# ANALOG_INPUT.net
KiCad netlist of a schematic drawn in Altium Designer
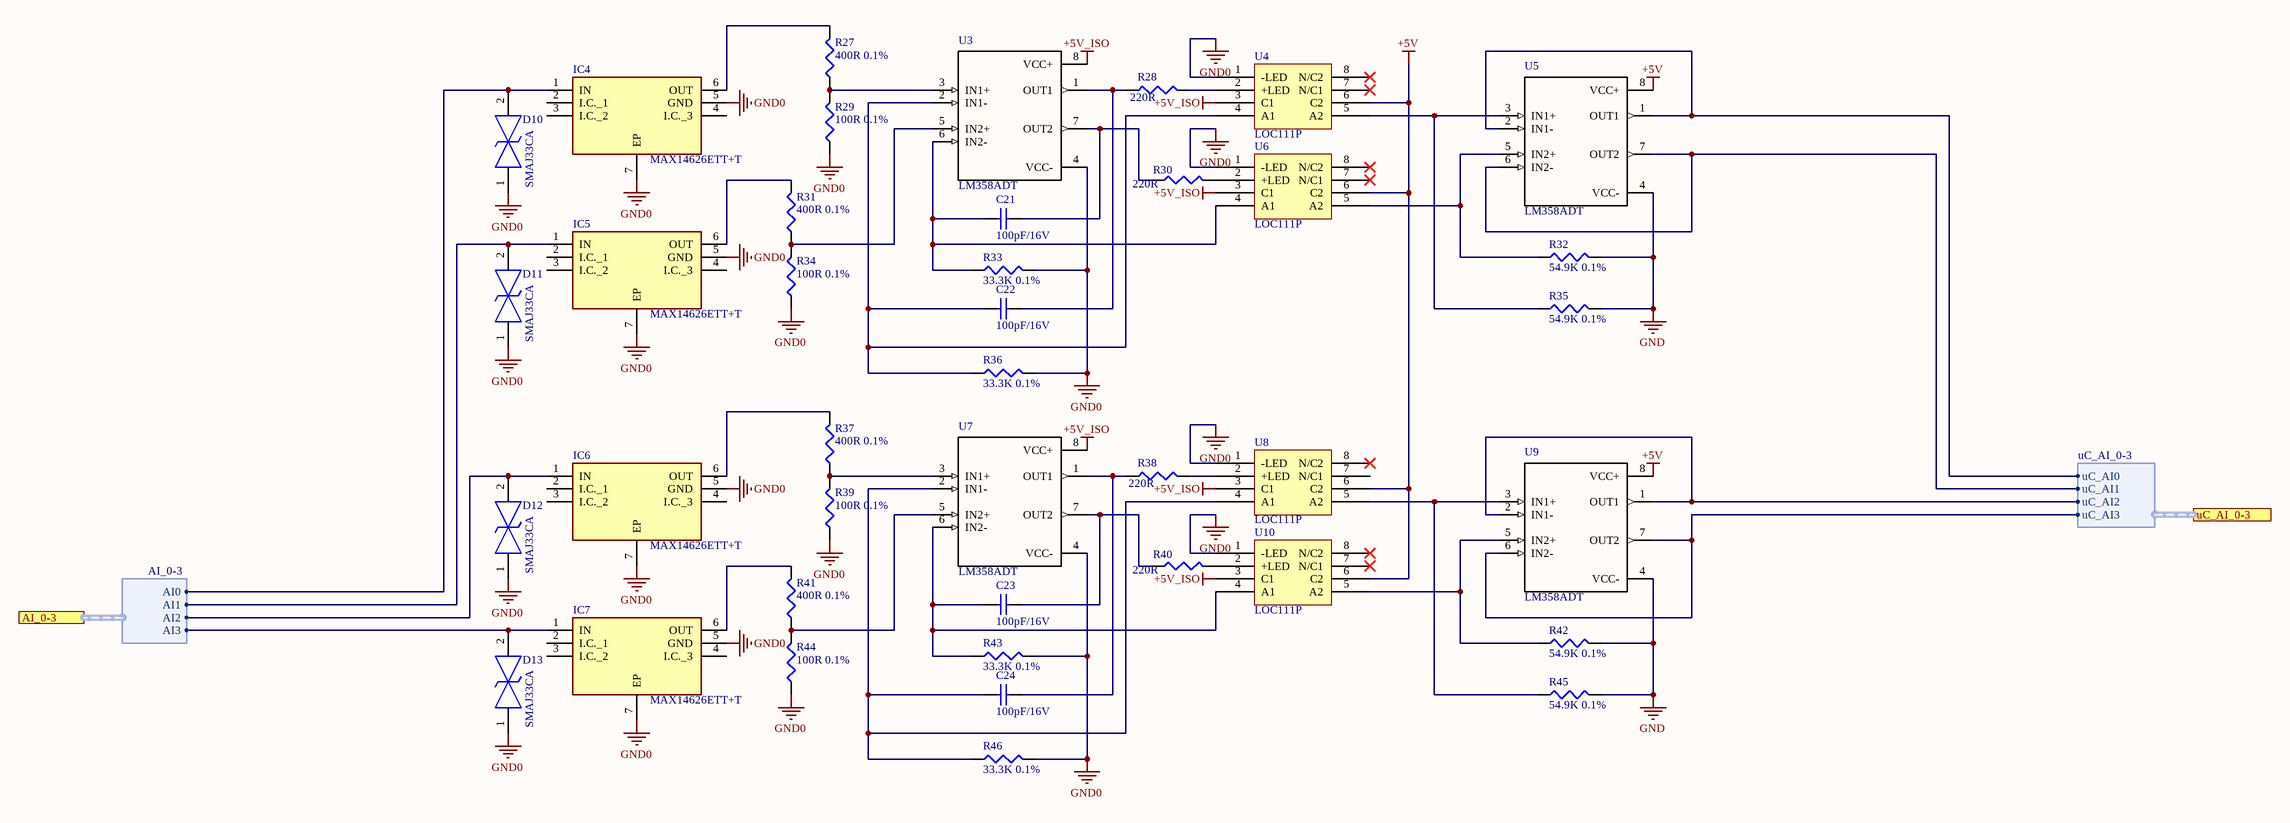
[diagram p0: ANALOG_INPUT.SchDoc]

(export (version "E")
  (design (tool "Eeschema 10.0.6"))
  (components
    (comp (ref "C21")
      (value "100pF/16V")
      (footprint "1608[0603]")
      (description "Capacitor (Semiconductor SIM Model)")
      (fields (field (name "PUBLISHER") "Altium Limited"))
      (libsource (lib "Miscellaneous Devices") (part "Cap Semi"))
    )
    (comp (ref "C22")
      (value "100pF/16V")
      (footprint "1608[0603]")
      (description "Capacitor (Semiconductor SIM Model)")
      (fields (field (name "PUBLISHER") "Altium Limited"))
      (libsource (lib "Miscellaneous Devices") (part "Cap Semi"))
    )
    (comp (ref "C23")
      (value "100pF/16V")
      (footprint "1608[0603]")
      (description "Capacitor (Semiconductor SIM Model)")
      (fields (field (name "PUBLISHER") "Altium Limited"))
      (libsource (lib "Miscellaneous Devices") (part "Cap Semi"))
    )
    (comp (ref "C24")
      (value "100pF/16V")
      (footprint "1608[0603]")
      (description "Capacitor (Semiconductor SIM Model)")
      (fields (field (name "PUBLISHER") "Altium Limited"))
      (libsource (lib "Miscellaneous Devices") (part "Cap Semi"))
    )
    (comp (ref "D10")
      (value "SMAJ33CA")
      (footprint "SamacSys:DIONM5126X250N")
      (description "TVS Diode (Bi-directional)")
      (fields (field (name "MOUSER PART NUMBER") "576-SMAJ33CA"))
      (libsource (lib "*") (part "SMAJ33CA"))
    )
    (comp (ref "D11")
      (value "SMAJ33CA")
      (footprint "SamacSys:DIONM5126X250N")
      (description "TVS Diode (Bi-directional)")
      (fields (field (name "MOUSER PART NUMBER") "576-SMAJ33CA"))
      (libsource (lib "*") (part "SMAJ33CA"))
    )
    (comp (ref "D12")
      (value "SMAJ33CA")
      (footprint "SamacSys:DIONM5126X250N")
      (description "TVS Diode (Bi-directional)")
      (fields (field (name "MOUSER PART NUMBER") "576-SMAJ33CA"))
      (libsource (lib "*") (part "SMAJ33CA"))
    )
    (comp (ref "D13")
      (value "SMAJ33CA")
      (footprint "SamacSys:DIONM5126X250N")
      (description "TVS Diode (Bi-directional)")
      (fields (field (name "MOUSER PART NUMBER") "576-SMAJ33CA"))
      (libsource (lib "*") (part "SMAJ33CA"))
    )
    (comp (ref "IC4")
      (value "MAX14626ETT+T")
      (footprint "SamacSys:SON95P300X300X80-7N")
      (description "Integrated Circuit")
      (fields (field (name "MOUSER PART NUMBER") "700-MAX14626ETT+T"))
      (libsource (lib "*") (part "MAX14626ETT+T"))
    )
    (comp (ref "IC5")
      (value "MAX14626ETT+T")
      (footprint "SamacSys:SON95P300X300X80-7N")
      (description "Integrated Circuit")
      (fields (field (name "MOUSER PART NUMBER") "700-MAX14626ETT+T"))
      (libsource (lib "*") (part "MAX14626ETT+T"))
    )
    (comp (ref "IC6")
      (value "MAX14626ETT+T")
      (footprint "SamacSys:SON95P300X300X80-7N")
      (description "Integrated Circuit")
      (fields (field (name "MOUSER PART NUMBER") "700-MAX14626ETT+T"))
      (libsource (lib "*") (part "MAX14626ETT+T"))
    )
    (comp (ref "IC7")
      (value "MAX14626ETT+T")
      (footprint "SamacSys:SON95P300X300X80-7N")
      (description "Integrated Circuit")
      (fields (field (name "MOUSER PART NUMBER") "700-MAX14626ETT+T"))
      (libsource (lib "*") (part "MAX14626ETT+T"))
    )
    (comp (ref "R27")
      (value "400R 0.1%")
      (footprint "C1206")
      (description "Resistor")
      (fields (field (name "PUBLISHER") "Altium Limited"))
      (libsource (lib "Miscellaneous Devices") (part "Res3"))
    )
    (comp (ref "R28")
      (value "220R")
      (footprint "J1-0603")
      (description "Resistor")
      (fields (field (name "PUBLISHER") "Altium Limited"))
      (libsource (lib "Miscellaneous Devices") (part "Res3"))
    )
    (comp (ref "R29")
      (value "100R 0.1%")
      (footprint "C1206")
      (description "Resistor")
      (fields (field (name "PUBLISHER") "Altium Limited"))
      (libsource (lib "Miscellaneous Devices") (part "Res3"))
    )
    (comp (ref "R30")
      (value "220R")
      (footprint "J1-0603")
      (description "Resistor")
      (fields (field (name "PUBLISHER") "Altium Limited"))
      (libsource (lib "Miscellaneous Devices") (part "Res3"))
    )
    (comp (ref "R31")
      (value "400R 0.1%")
      (footprint "C1206")
      (description "Resistor")
      (fields (field (name "PUBLISHER") "Altium Limited"))
      (libsource (lib "Miscellaneous Devices") (part "Res3"))
    )
    (comp (ref "R32")
      (value "54.9K 0.1%")
      (footprint "J1-0603")
      (description "Resistor")
      (fields (field (name "PUBLISHER") "Altium Limited"))
      (libsource (lib "Miscellaneous Devices") (part "Res3"))
    )
    (comp (ref "R33")
      (value "33.3K 0.1%")
      (footprint "J1-0603")
      (description "Resistor")
      (fields (field (name "PUBLISHER") "Altium Limited"))
      (libsource (lib "Miscellaneous Devices") (part "Res3"))
    )
    (comp (ref "R34")
      (value "100R 0.1%")
      (footprint "C1206")
      (description "Resistor")
      (fields (field (name "PUBLISHER") "Altium Limited"))
      (libsource (lib "Miscellaneous Devices") (part "Res3"))
    )
    (comp (ref "R35")
      (value "54.9K 0.1%")
      (footprint "J1-0603")
      (description "Resistor")
      (fields (field (name "PUBLISHER") "Altium Limited"))
      (libsource (lib "Miscellaneous Devices") (part "Res3"))
    )
    (comp (ref "R36")
      (value "33.3K 0.1%")
      (footprint "J1-0603")
      (description "Resistor")
      (fields (field (name "PUBLISHER") "Altium Limited"))
      (libsource (lib "Miscellaneous Devices") (part "Res3"))
    )
    (comp (ref "R37")
      (value "400R 0.1%")
      (footprint "C1206")
      (description "Resistor")
      (fields (field (name "PUBLISHER") "Altium Limited"))
      (libsource (lib "Miscellaneous Devices") (part "Res3"))
    )
    (comp (ref "R38")
      (value "220R")
      (footprint "J1-0603")
      (description "Resistor")
      (fields (field (name "PUBLISHER") "Altium Limited"))
      (libsource (lib "Miscellaneous Devices") (part "Res3"))
    )
    (comp (ref "R39")
      (value "100R 0.1%")
      (footprint "C1206")
      (description "Resistor")
      (fields (field (name "PUBLISHER") "Altium Limited"))
      (libsource (lib "Miscellaneous Devices") (part "Res3"))
    )
    (comp (ref "R40")
      (value "220R")
      (footprint "J1-0603")
      (description "Resistor")
      (fields (field (name "PUBLISHER") "Altium Limited"))
      (libsource (lib "Miscellaneous Devices") (part "Res3"))
    )
    (comp (ref "R41")
      (value "400R 0.1%")
      (footprint "C1206")
      (description "Resistor")
      (fields (field (name "PUBLISHER") "Altium Limited"))
      (libsource (lib "Miscellaneous Devices") (part "Res3"))
    )
    (comp (ref "R42")
      (value "54.9K 0.1%")
      (footprint "J1-0603")
      (description "Resistor")
      (fields (field (name "PUBLISHER") "Altium Limited"))
      (libsource (lib "Miscellaneous Devices") (part "Res3"))
    )
    (comp (ref "R43")
      (value "33.3K 0.1%")
      (footprint "J1-0603")
      (description "Resistor")
      (fields (field (name "PUBLISHER") "Altium Limited"))
      (libsource (lib "Miscellaneous Devices") (part "Res3"))
    )
    (comp (ref "R44")
      (value "100R 0.1%")
      (footprint "C1206")
      (description "Resistor")
      (fields (field (name "PUBLISHER") "Altium Limited"))
      (libsource (lib "Miscellaneous Devices") (part "Res3"))
    )
    (comp (ref "R45")
      (value "54.9K 0.1%")
      (footprint "J1-0603")
      (description "Resistor")
      (fields (field (name "PUBLISHER") "Altium Limited"))
      (libsource (lib "Miscellaneous Devices") (part "Res3"))
    )
    (comp (ref "R46")
      (value "33.3K 0.1%")
      (footprint "J1-0603")
      (description "Resistor")
      (fields (field (name "PUBLISHER") "Altium Limited"))
      (libsource (lib "Miscellaneous Devices") (part "Res3"))
    )
    (comp (ref "U3")
      (value "LM358ADT")
      (footprint "*SOIC127P600X175-8N")
      (description "LM358 Series 30 V 1.1 MHz Low Power Dual Operational Amplifier - SOIC-8")
      (fields (field (name "MF") "STMicroelectronics"))
      (libsource (lib "BV100011_UniversalSlave") (part "LM358ADT"))
    )
    (comp (ref "U4")
      (value "LOC111P")
      (footprint "SOP254P940X265-8N")
      (description "Linear Optocoupler")
      (libsource (lib "BV100011_UniversalSlave") (part "LOC111P"))
    )
    (comp (ref "U5")
      (value "LM358ADT")
      (footprint "*SOIC127P600X175-8N")
      (description "LM358 Series 30 V 1.1 MHz Low Power Dual Operational Amplifier - SOIC-8")
      (fields (field (name "MF") "STMicroelectronics"))
      (libsource (lib "BV100011_UniversalSlave") (part "LM358ADT"))
    )
    (comp (ref "U6")
      (value "LOC111P")
      (footprint "SOP254P940X265-8N")
      (description "Linear Optocoupler")
      (libsource (lib "BV100011_UniversalSlave") (part "LOC111P"))
    )
    (comp (ref "U7")
      (value "LM358ADT")
      (footprint "*SOIC127P600X175-8N")
      (description "LM358 Series 30 V 1.1 MHz Low Power Dual Operational Amplifier - SOIC-8")
      (fields (field (name "MF") "STMicroelectronics"))
      (libsource (lib "BV100011_UniversalSlave") (part "LM358ADT"))
    )
    (comp (ref "U8")
      (value "LOC111P")
      (footprint "SOP254P940X265-8N")
      (description "Linear Optocoupler")
      (libsource (lib "BV100011_UniversalSlave") (part "LOC111P"))
    )
    (comp (ref "U9")
      (value "LM358ADT")
      (footprint "*SOIC127P600X175-8N")
      (description "LM358 Series 30 V 1.1 MHz Low Power Dual Operational Amplifier - SOIC-8")
      (fields (field (name "MF") "STMicroelectronics"))
      (libsource (lib "BV100011_UniversalSlave") (part "LM358ADT"))
    )
    (comp (ref "U10")
      (value "LOC111P")
      (footprint "SOP254P940X265-8N")
      (description "Linear Optocoupler")
      (libsource (lib "BV100011_UniversalSlave") (part "LOC111P"))
    )
  )
  (nets
    (net (code "3") (name "+5V") (class "Default")
      (node (ref "U10") (pin "6") (pinfunction "C2_6") (pintype "passive"))
      (node (ref "U4") (pin "6") (pinfunction "C2_6") (pintype "passive"))
      (node (ref "U5") (pin "8") (pinfunction "VCC+_8") (pintype "power_in"))
      (node (ref "U6") (pin "6") (pinfunction "C2_6") (pintype "passive"))
      (node (ref "U8") (pin "6") (pinfunction "C2_6") (pintype "passive"))
      (node (ref "U9") (pin "8") (pinfunction "VCC+_8") (pintype "power_in"))
    )
    (net (code "4") (name "+5V_ISO") (class "Default")
      (node (ref "U10") (pin "3") (pinfunction "C1_3") (pintype "passive"))
      (node (ref "U3") (pin "8") (pinfunction "VCC+_8") (pintype "power_in"))
      (node (ref "U4") (pin "3") (pinfunction "C1_3") (pintype "passive"))
      (node (ref "U6") (pin "3") (pinfunction "C1_3") (pintype "passive"))
      (node (ref "U7") (pin "8") (pinfunction "VCC+_8") (pintype "power_in"))
      (node (ref "U8") (pin "3") (pinfunction "C1_3") (pintype "passive"))
    )
    (net (code "7") (name "GND") (class "Default")
      (node (ref "R32") (pin "2") (pinfunction "2_2") (pintype "passive"))
      (node (ref "R35") (pin "2") (pinfunction "2_2") (pintype "passive"))
      (node (ref "R42") (pin "2") (pinfunction "2_2") (pintype "passive"))
      (node (ref "R45") (pin "2") (pinfunction "2_2") (pintype "passive"))
      (node (ref "U5") (pin "4") (pinfunction "VCC-_4") (pintype "power_in"))
      (node (ref "U9") (pin "4") (pinfunction "VCC-_4") (pintype "power_in"))
    )
    (net (code "8") (name "GND0") (class "Default")
      (node (ref "D10") (pin "1") (pinfunction "1_1") (pintype "passive"))
      (node (ref "D11") (pin "1") (pinfunction "1_1") (pintype "passive"))
      (node (ref "D12") (pin "1") (pinfunction "1_1") (pintype "passive"))
      (node (ref "D13") (pin "1") (pinfunction "1_1") (pintype "passive"))
      (node (ref "IC4") (pin "5") (pinfunction "GND_5") (pintype "passive"))
      (node (ref "IC4") (pin "7") (pinfunction "EP_7") (pintype "passive"))
      (node (ref "IC5") (pin "5") (pinfunction "GND_5") (pintype "passive"))
      (node (ref "IC5") (pin "7") (pinfunction "EP_7") (pintype "passive"))
      (node (ref "IC6") (pin "5") (pinfunction "GND_5") (pintype "passive"))
      (node (ref "IC6") (pin "7") (pinfunction "EP_7") (pintype "passive"))
      (node (ref "IC7") (pin "5") (pinfunction "GND_5") (pintype "passive"))
      (node (ref "IC7") (pin "7") (pinfunction "EP_7") (pintype "passive"))
      (node (ref "R29") (pin "1") (pinfunction "1_1") (pintype "passive"))
      (node (ref "R33") (pin "2") (pinfunction "2_2") (pintype "passive"))
      (node (ref "R34") (pin "1") (pinfunction "1_1") (pintype "passive"))
      (node (ref "R36") (pin "2") (pinfunction "2_2") (pintype "passive"))
      (node (ref "R39") (pin "1") (pinfunction "1_1") (pintype "passive"))
      (node (ref "R43") (pin "2") (pinfunction "2_2") (pintype "passive"))
      (node (ref "R44") (pin "1") (pinfunction "1_1") (pintype "passive"))
      (node (ref "R46") (pin "2") (pinfunction "2_2") (pintype "passive"))
      (node (ref "U10") (pin "1") (pinfunction "-LED_1") (pintype "passive"))
      (node (ref "U3") (pin "4") (pinfunction "VCC-_4") (pintype "power_in"))
      (node (ref "U4") (pin "1") (pinfunction "-LED_1") (pintype "passive"))
      (node (ref "U6") (pin "1") (pinfunction "-LED_1") (pintype "passive"))
      (node (ref "U7") (pin "4") (pinfunction "VCC-_4") (pintype "power_in"))
      (node (ref "U8") (pin "1") (pinfunction "-LED_1") (pintype "passive"))
    )
    (net (code "9") (name "Net-(IC4-IN)") (class "Default")
      (node (ref "D10") (pin "2") (pinfunction "2_2") (pintype "passive"))
      (node (ref "IC4") (pin "1") (pinfunction "IN_1") (pintype "passive"))
    )
    (net (code "10") (name "Net-(IC4-OUT)") (class "Default")
      (node (ref "IC4") (pin "6") (pinfunction "OUT_6") (pintype "passive"))
      (node (ref "R27") (pin "2") (pinfunction "2_2") (pintype "passive"))
    )
    (net (code "11") (name "Net-(IC5-IN)") (class "Default")
      (node (ref "D11") (pin "2") (pinfunction "2_2") (pintype "passive"))
      (node (ref "IC5") (pin "1") (pinfunction "IN_1") (pintype "passive"))
    )
    (net (code "12") (name "Net-(IC5-OUT)") (class "Default")
      (node (ref "IC5") (pin "6") (pinfunction "OUT_6") (pintype "passive"))
      (node (ref "R31") (pin "2") (pinfunction "2_2") (pintype "passive"))
    )
    (net (code "13") (name "Net-(IC6-IN)") (class "Default")
      (node (ref "D12") (pin "2") (pinfunction "2_2") (pintype "passive"))
      (node (ref "IC6") (pin "1") (pinfunction "IN_1") (pintype "passive"))
    )
    (net (code "14") (name "Net-(IC6-OUT)") (class "Default")
      (node (ref "IC6") (pin "6") (pinfunction "OUT_6") (pintype "passive"))
      (node (ref "R37") (pin "2") (pinfunction "2_2") (pintype "passive"))
    )
    (net (code "15") (name "Net-(IC7-IN)") (class "Default")
      (node (ref "D13") (pin "2") (pinfunction "2_2") (pintype "passive"))
      (node (ref "IC7") (pin "1") (pinfunction "IN_1") (pintype "passive"))
    )
    (net (code "16") (name "Net-(IC7-OUT)") (class "Default")
      (node (ref "IC7") (pin "6") (pinfunction "OUT_6") (pintype "passive"))
      (node (ref "R41") (pin "2") (pinfunction "2_2") (pintype "passive"))
    )
    (net (code "17") (name "Net-(U3-IN1+)") (class "Default")
      (node (ref "R27") (pin "1") (pinfunction "1_1") (pintype "passive"))
      (node (ref "R29") (pin "2") (pinfunction "2_2") (pintype "passive"))
      (node (ref "U3") (pin "3") (pinfunction "IN1+_3") (pintype "input"))
    )
    (net (code "18") (name "Net-(U3-IN1-)") (class "Default")
      (node (ref "C22") (pin "1") (pinfunction "1_1") (pintype "passive"))
      (node (ref "R36") (pin "1") (pinfunction "1_1") (pintype "passive"))
      (node (ref "U3") (pin "2") (pinfunction "IN1-_2") (pintype "input"))
      (node (ref "U4") (pin "4") (pinfunction "A1_4") (pintype "passive"))
    )
    (net (code "19") (name "Net-(U3-IN2+)") (class "Default")
      (node (ref "R31") (pin "1") (pinfunction "1_1") (pintype "passive"))
      (node (ref "R34") (pin "2") (pinfunction "2_2") (pintype "passive"))
      (node (ref "U3") (pin "5") (pinfunction "IN2+_5") (pintype "input"))
    )
    (net (code "20") (name "Net-(U3-IN2-)") (class "Default")
      (node (ref "C21") (pin "1") (pinfunction "1_1") (pintype "passive"))
      (node (ref "R33") (pin "1") (pinfunction "1_1") (pintype "passive"))
      (node (ref "U3") (pin "6") (pinfunction "IN2-_6") (pintype "input"))
      (node (ref "U6") (pin "4") (pinfunction "A1_4") (pintype "passive"))
    )
    (net (code "21") (name "Net-(U3-OUT1)") (class "Default")
      (node (ref "C22") (pin "2") (pinfunction "2_2") (pintype "passive"))
      (node (ref "R28") (pin "1") (pinfunction "1_1") (pintype "passive"))
      (node (ref "U3") (pin "1") (pinfunction "OUT1_1") (pintype "output"))
    )
    (net (code "22") (name "Net-(U3-OUT2)") (class "Default")
      (node (ref "C21") (pin "2") (pinfunction "2_2") (pintype "passive"))
      (node (ref "R30") (pin "1") (pinfunction "1_1") (pintype "passive"))
      (node (ref "U3") (pin "7") (pinfunction "OUT2_7") (pintype "output"))
    )
    (net (code "23") (name "Net-(U4-+LED)") (class "Default")
      (node (ref "R28") (pin "2") (pinfunction "2_2") (pintype "passive"))
      (node (ref "U4") (pin "2") (pinfunction "+LED_2") (pintype "passive"))
    )
    (net (code "24") (name "Net-(U4-A2)") (class "Default")
      (node (ref "R35") (pin "1") (pinfunction "1_1") (pintype "passive"))
      (node (ref "U4") (pin "5") (pinfunction "A2_5") (pintype "passive"))
      (node (ref "U5") (pin "3") (pinfunction "IN1+_3") (pintype "input"))
    )
    (net (code "25") (name "Net-(U5-IN1-)") (class "Default")
      (node (ref "U5") (pin "1") (pinfunction "OUT1_1") (pintype "output"))
      (node (ref "U5") (pin "2") (pinfunction "IN1-_2") (pintype "input"))
    )
    (net (code "26") (name "Net-(U5-IN2+)") (class "Default")
      (node (ref "R32") (pin "1") (pinfunction "1_1") (pintype "passive"))
      (node (ref "U5") (pin "5") (pinfunction "IN2+_5") (pintype "input"))
      (node (ref "U6") (pin "5") (pinfunction "A2_5") (pintype "passive"))
    )
    (net (code "27") (name "Net-(U5-IN2-)") (class "Default")
      (node (ref "U5") (pin "6") (pinfunction "IN2-_6") (pintype "input"))
      (node (ref "U5") (pin "7") (pinfunction "OUT2_7") (pintype "output"))
    )
    (net (code "28") (name "Net-(U6-+LED)") (class "Default")
      (node (ref "R30") (pin "2") (pinfunction "2_2") (pintype "passive"))
      (node (ref "U6") (pin "2") (pinfunction "+LED_2") (pintype "passive"))
    )
    (net (code "29") (name "Net-(U7-IN1+)") (class "Default")
      (node (ref "R37") (pin "1") (pinfunction "1_1") (pintype "passive"))
      (node (ref "R39") (pin "2") (pinfunction "2_2") (pintype "passive"))
      (node (ref "U7") (pin "3") (pinfunction "IN1+_3") (pintype "input"))
    )
    (net (code "30") (name "Net-(U7-IN1-)") (class "Default")
      (node (ref "C24") (pin "1") (pinfunction "1_1") (pintype "passive"))
      (node (ref "R46") (pin "1") (pinfunction "1_1") (pintype "passive"))
      (node (ref "U7") (pin "2") (pinfunction "IN1-_2") (pintype "input"))
      (node (ref "U8") (pin "4") (pinfunction "A1_4") (pintype "passive"))
    )
    (net (code "31") (name "Net-(U7-IN2+)") (class "Default")
      (node (ref "R41") (pin "1") (pinfunction "1_1") (pintype "passive"))
      (node (ref "R44") (pin "2") (pinfunction "2_2") (pintype "passive"))
      (node (ref "U7") (pin "5") (pinfunction "IN2+_5") (pintype "input"))
    )
    (net (code "32") (name "Net-(U7-OUT1)") (class "Default")
      (node (ref "C24") (pin "2") (pinfunction "2_2") (pintype "passive"))
      (node (ref "R38") (pin "1") (pinfunction "1_1") (pintype "passive"))
      (node (ref "U7") (pin "1") (pinfunction "OUT1_1") (pintype "output"))
    )
    (net (code "33") (name "Net-(U7-OUT2)") (class "Default")
      (node (ref "C23") (pin "2") (pinfunction "2_2") (pintype "passive"))
      (node (ref "R40") (pin "1") (pinfunction "1_1") (pintype "passive"))
      (node (ref "U7") (pin "7") (pinfunction "OUT2_7") (pintype "output"))
    )
    (net (code "34") (name "Net-(U8-+LED)") (class "Default")
      (node (ref "R38") (pin "2") (pinfunction "2_2") (pintype "passive"))
      (node (ref "U8") (pin "2") (pinfunction "+LED_2") (pintype "passive"))
    )
    (net (code "35") (name "Net-(U8-A2)") (class "Default")
      (node (ref "R45") (pin "1") (pinfunction "1_1") (pintype "passive"))
      (node (ref "U8") (pin "5") (pinfunction "A2_5") (pintype "passive"))
      (node (ref "U9") (pin "3") (pinfunction "IN1+_3") (pintype "input"))
    )
    (net (code "36") (name "Net-(U9-IN1-)") (class "Default")
      (node (ref "U9") (pin "1") (pinfunction "OUT1_1") (pintype "output"))
      (node (ref "U9") (pin "2") (pinfunction "IN1-_2") (pintype "input"))
    )
    (net (code "37") (name "Net-(U9-IN2-)") (class "Default")
      (node (ref "U9") (pin "6") (pinfunction "IN2-_6") (pintype "input"))
      (node (ref "U9") (pin "7") (pinfunction "OUT2_7") (pintype "output"))
    )
    (net (code "38") (name "Net-(U10-+LED)") (class "Default")
      (node (ref "R40") (pin "2") (pinfunction "2_2") (pintype "passive"))
      (node (ref "U10") (pin "2") (pinfunction "+LED_2") (pintype "passive"))
    )
    (net (code "39") (name "Net-(U10-A1)") (class "Default")
      (node (ref "C23") (pin "1") (pinfunction "1_1") (pintype "passive"))
      (node (ref "R43") (pin "1") (pinfunction "1_1") (pintype "passive"))
      (node (ref "U10") (pin "4") (pinfunction "A1_4") (pintype "passive"))
      (node (ref "U7") (pin "6") (pinfunction "IN2-_6") (pintype "input"))
    )
    (net (code "40") (name "Net-(U10-A2)") (class "Default")
      (node (ref "R42") (pin "1") (pinfunction "1_1") (pintype "passive"))
      (node (ref "U10") (pin "5") (pinfunction "A2_5") (pintype "passive"))
      (node (ref "U9") (pin "5") (pinfunction "IN2+_5") (pintype "input"))
    )
    (net (code "41") (name "unconnected-(IC4-I.C._1-Pad2)") (class "Default")
      (node (ref "IC4") (pin "2") (pinfunction "I.C._1_2") (pintype "passive"))
    )
    (net (code "42") (name "unconnected-(IC4-I.C._2-Pad3)") (class "Default")
      (node (ref "IC4") (pin "3") (pinfunction "I.C._2_3") (pintype "passive"))
    )
    (net (code "43") (name "unconnected-(IC4-I.C._3-Pad4)") (class "Default")
      (node (ref "IC4") (pin "4") (pinfunction "I.C._3_4") (pintype "passive"))
    )
    (net (code "44") (name "unconnected-(IC5-I.C._1-Pad2)") (class "Default")
      (node (ref "IC5") (pin "2") (pinfunction "I.C._1_2") (pintype "passive"))
    )
    (net (code "45") (name "unconnected-(IC5-I.C._2-Pad3)") (class "Default")
      (node (ref "IC5") (pin "3") (pinfunction "I.C._2_3") (pintype "passive"))
    )
    (net (code "46") (name "unconnected-(IC5-I.C._3-Pad4)") (class "Default")
      (node (ref "IC5") (pin "4") (pinfunction "I.C._3_4") (pintype "passive"))
    )
    (net (code "47") (name "unconnected-(IC6-I.C._1-Pad2)") (class "Default")
      (node (ref "IC6") (pin "2") (pinfunction "I.C._1_2") (pintype "passive"))
    )
    (net (code "48") (name "unconnected-(IC6-I.C._2-Pad3)") (class "Default")
      (node (ref "IC6") (pin "3") (pinfunction "I.C._2_3") (pintype "passive"))
    )
    (net (code "49") (name "unconnected-(IC6-I.C._3-Pad4)") (class "Default")
      (node (ref "IC6") (pin "4") (pinfunction "I.C._3_4") (pintype "passive"))
    )
    (net (code "50") (name "unconnected-(IC7-I.C._1-Pad2)") (class "Default")
      (node (ref "IC7") (pin "2") (pinfunction "I.C._1_2") (pintype "passive"))
    )
    (net (code "51") (name "unconnected-(IC7-I.C._2-Pad3)") (class "Default")
      (node (ref "IC7") (pin "3") (pinfunction "I.C._2_3") (pintype "passive"))
    )
    (net (code "52") (name "unconnected-(IC7-I.C._3-Pad4)") (class "Default")
      (node (ref "IC7") (pin "4") (pinfunction "I.C._3_4") (pintype "passive"))
    )
    (net (code "53") (name "unconnected-(U4-N{slash}C1-Pad7)") (class "Default")
      (node (ref "U4") (pin "7") (pinfunction "N/C1_7") (pintype "passive+no_connect"))
    )
    (net (code "54") (name "unconnected-(U4-N{slash}C2-Pad8)") (class "Default")
      (node (ref "U4") (pin "8") (pinfunction "N/C2_8") (pintype "passive+no_connect"))
    )
    (net (code "55") (name "unconnected-(U6-N{slash}C1-Pad7)") (class "Default")
      (node (ref "U6") (pin "7") (pinfunction "N/C1_7") (pintype "passive+no_connect"))
    )
    (net (code "56") (name "unconnected-(U6-N{slash}C2-Pad8)") (class "Default")
      (node (ref "U6") (pin "8") (pinfunction "N/C2_8") (pintype "passive+no_connect"))
    )
    (net (code "57") (name "unconnected-(U8-N{slash}C1-Pad7)") (class "Default")
      (node (ref "U8") (pin "7") (pinfunction "N/C1_7") (pintype "passive"))
    )
    (net (code "58") (name "unconnected-(U8-N{slash}C2-Pad8)") (class "Default")
      (node (ref "U8") (pin "8") (pinfunction "N/C2_8") (pintype "passive+no_connect"))
    )
    (net (code "59") (name "unconnected-(U10-N{slash}C1-Pad7)") (class "Default")
      (node (ref "U10") (pin "7") (pinfunction "N/C1_7") (pintype "passive+no_connect"))
    )
    (net (code "60") (name "unconnected-(U10-N{slash}C2-Pad8)") (class "Default")
      (node (ref "U10") (pin "8") (pinfunction "N/C2_8") (pintype "passive+no_connect"))
    )
  )
)
